# TopLevelDesgin.net
KiCad netlist of a schematic drawn in Altium Designer
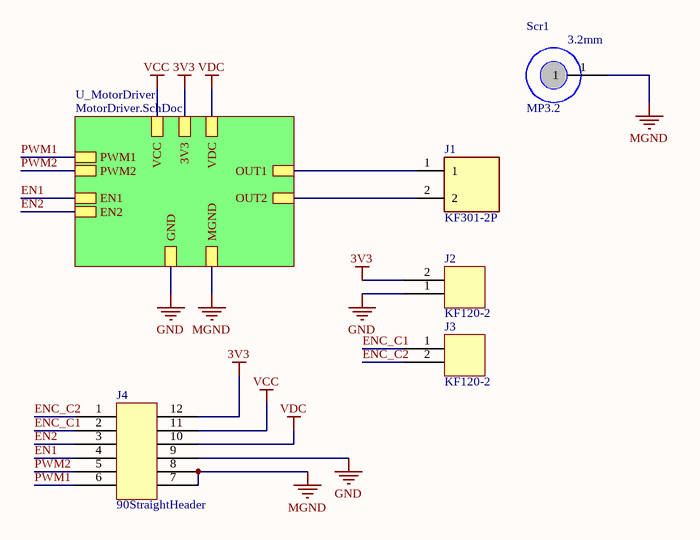
[diagram p0: TopLevelDesgin.SchDoc]

(export (version "E")
  (design (tool "Eeschema 10.0.6"))
  (components
    (comp (ref "J1")
      (value "KF301-2P")
      (footprint "HANDSON_KF301-2P")
      (description "2 Pin Terminal Block 5mm Pitch")
      (libsource (lib "Tin Tran") (part "KF301-2P"))
    )
    (comp (ref "J2")
      (value "KF120-2")
      (footprint "KF120-2-Footprint-1")
      (description "2.54mm Terminal")
      (libsource (lib "") (part "KF120-2-Symbol-1_1"))
    )
    (comp (ref "J3")
      (value "KF120-2")
      (footprint "KF120-2-Footprint-1")
      (description "2.54mm Terminal")
      (libsource (lib "Tin Tran") (part "KF120-2-Symbol-1"))
    )
    (comp (ref "J4")
      (value "90StraightHeader")
      (footprint "Header90Degree")
      (libsource (lib "Tin Tran") (part "Header"))
    )
    (comp (ref "Scr1") (value "MP3.2") (footprint "MP3.2") (libsource (lib "Tin Tran") (part "MP3.2")))
  )
  (nets
    (net (code "1") (name "/EN1") (class "Default") (node (ref "J4") (pin "4") (pintype "passive")))
    (net (code "2") (name "/EN2") (class "Default") (node (ref "J4") (pin "3") (pintype "passive")))
    (net (code "3") (name "/ENC_C1") (class "Default")
      (node (ref "J3") (pin "1") (pinfunction "1_1") (pintype "passive"))
      (node (ref "J4") (pin "2") (pintype "passive"))
    )
    (net (code "4") (name "/ENC_C2") (class "Default")
      (node (ref "J3") (pin "2") (pinfunction "2_2") (pintype "passive"))
      (node (ref "J4") (pin "1") (pintype "passive"))
    )
    (net (code "5") (name "/OUT1") (class "Default")
      (node (ref "J1") (pin "1") (pinfunction "1_1") (pintype "passive"))
    )
    (net (code "6") (name "/OUT2") (class "Default")
      (node (ref "J1") (pin "2") (pinfunction "2_2") (pintype "passive"))
    )
    (net (code "7") (name "/PWM1") (class "Default") (node (ref "J4") (pin "6") (pintype "passive")))
    (net (code "8") (name "/PWM2") (class "Default") (node (ref "J4") (pin "5") (pintype "passive")))
    (net (code "9") (name "3V3") (class "Default")
      (node (ref "J2") (pin "2") (pinfunction "2_2") (pintype "passive"))
      (node (ref "J4") (pin "12") (pintype "passive"))
    )
    (net (code "10") (name "GND") (class "Default")
      (node (ref "J2") (pin "1") (pinfunction "1_1") (pintype "passive"))
      (node (ref "J4") (pin "9") (pintype "passive"))
    )
    (net (code "11") (name "MGND") (class "Default")
      (node (ref "J4") (pin "7") (pintype "passive"))
      (node (ref "J4") (pin "8") (pintype "passive"))
      (node (ref "Scr1") (pin "1") (pinfunction "1_1") (pintype "passive"))
    )
    (net (code "12") (name "VCC") (class "Default") (node (ref "J4") (pin "11") (pintype "passive")))
    (net (code "13") (name "VDC") (class "Default") (node (ref "J4") (pin "10") (pintype "passive")))
  )
)
